# controller.net
KiCad netlist of a schematic drawn in EAGLE
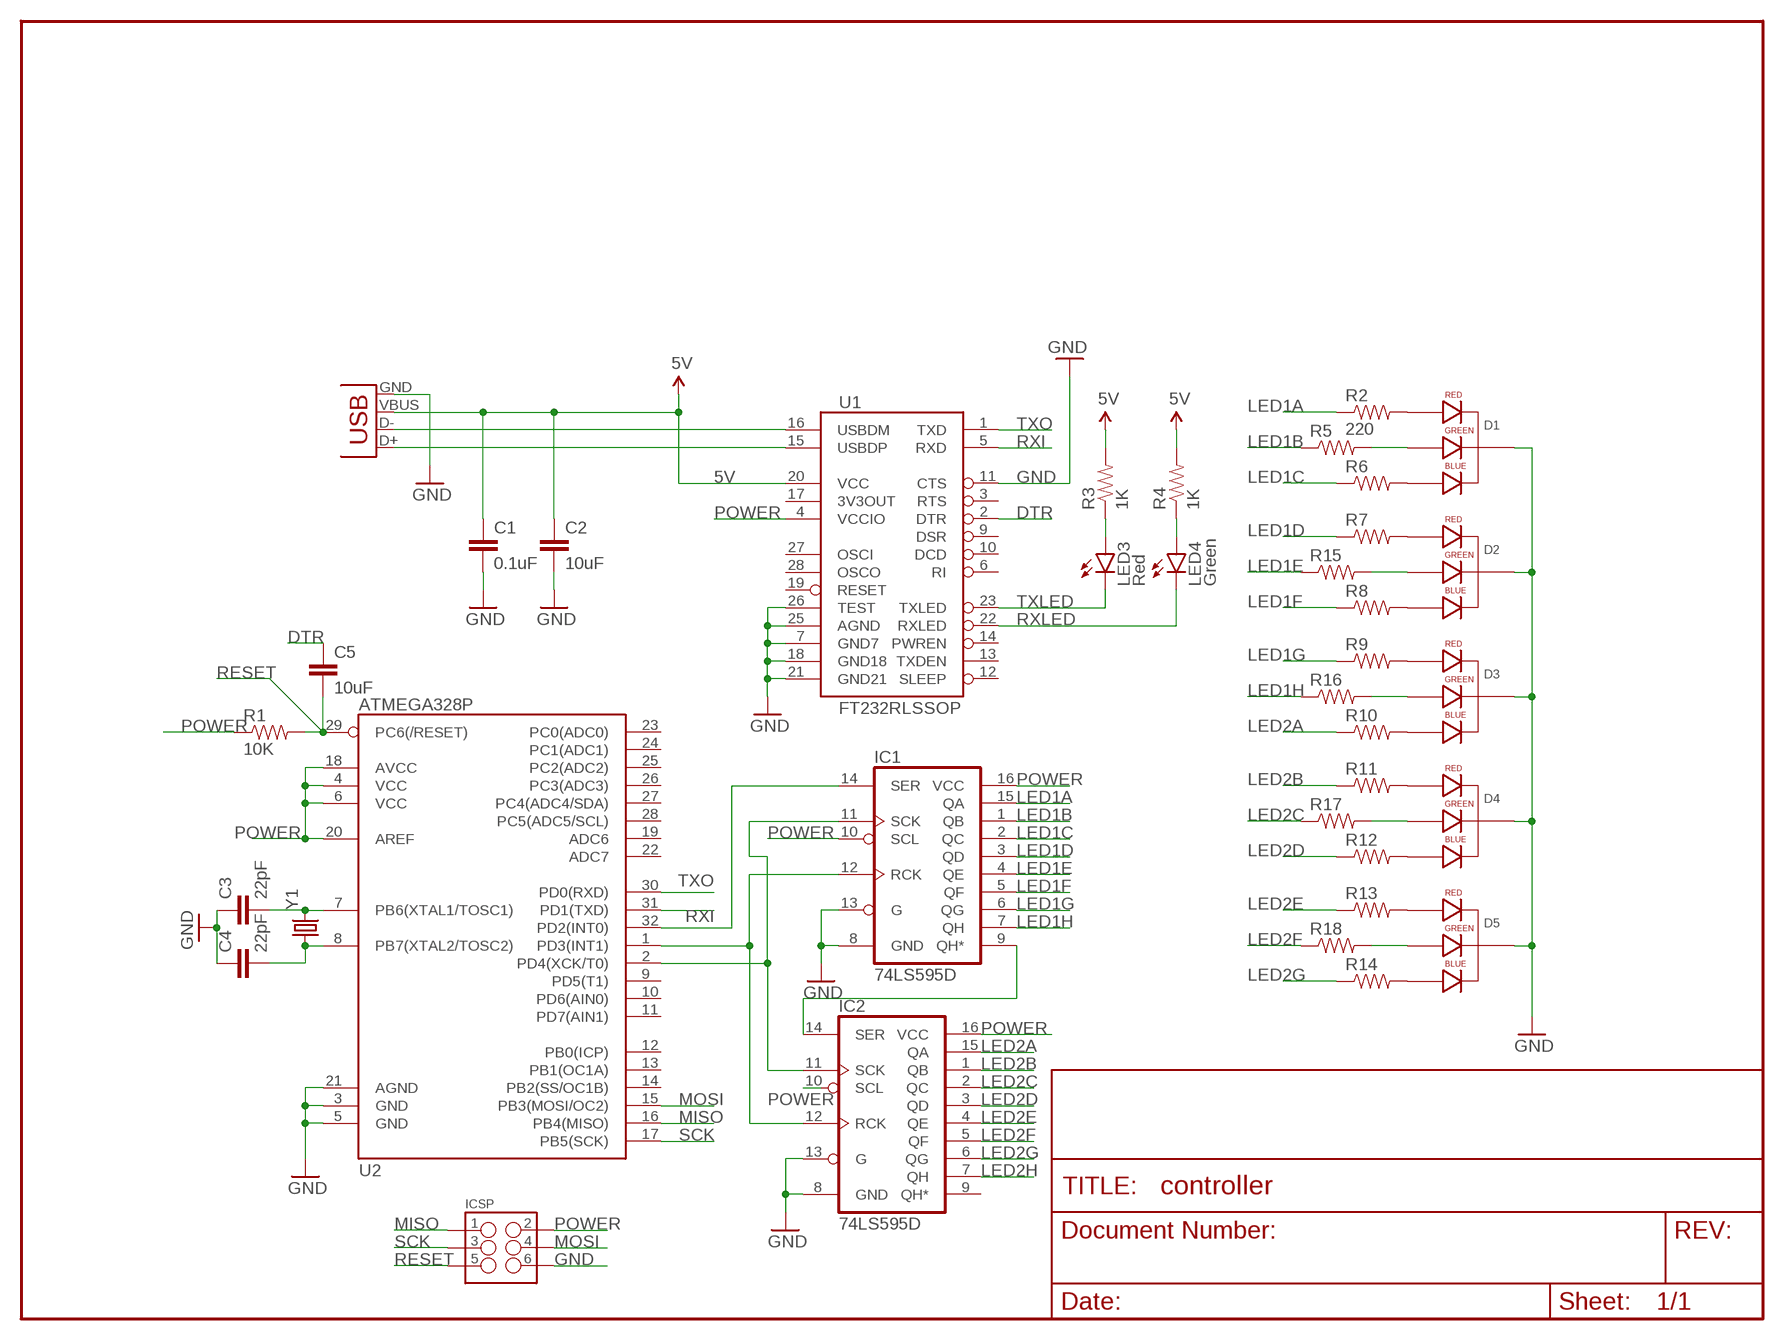
[diagram p0: schematic, sheet 1]

(export (version "E")
  (design (tool "Eeschema 10.0.6"))
  (components
    (comp (ref "C1")
      (value "0.1uF")
      (footprint "eagle-import:0805")
      (libsource (lib "eagle-import") (part "CAP0805"))
    )
    (comp (ref "C2")
      (value "10uF")
      (footprint "eagle-import:0805")
      (libsource (lib "eagle-import") (part "CAP0805"))
    )
    (comp (ref "C3")
      (value "22pF")
      (footprint "eagle-import:0805")
      (libsource (lib "eagle-import") (part "CAP0805"))
    )
    (comp (ref "C4")
      (value "22pF")
      (footprint "eagle-import:0805")
      (libsource (lib "eagle-import") (part "CAP0805"))
    )
    (comp (ref "C5")
      (value "10uF")
      (footprint "eagle-import:0805")
      (libsource (lib "eagle-import") (part "CAP0805"))
    )
    (comp (ref "D1")
      (value "LED-RGB-CC-THRUDIFFUSE")
      (footprint "eagle-import:LED-RGB-THRU")
      (libsource (lib "eagle-import") (part "LED-RGB-CC-THRUDIFFUSE"))
    )
    (comp (ref "D2")
      (value "LED-RGB-CC-THRUDIFFUSE")
      (footprint "eagle-import:LED-RGB-THRU")
      (libsource (lib "eagle-import") (part "LED-RGB-CC-THRUDIFFUSE"))
    )
    (comp (ref "D3")
      (value "LED-RGB-CC-THRUDIFFUSE")
      (footprint "eagle-import:LED-RGB-THRU")
      (libsource (lib "eagle-import") (part "LED-RGB-CC-THRUDIFFUSE"))
    )
    (comp (ref "D4")
      (value "LED-RGB-CC-THRUDIFFUSE")
      (footprint "eagle-import:LED-RGB-THRU")
      (libsource (lib "eagle-import") (part "LED-RGB-CC-THRUDIFFUSE"))
    )
    (comp (ref "D5")
      (value "LED-RGB-CC-THRUDIFFUSE")
      (footprint "eagle-import:LED-RGB-THRU")
      (libsource (lib "eagle-import") (part "LED-RGB-CC-THRUDIFFUSE"))
    )
    (comp (ref "IC1")
      (value "74LS595D")
      (footprint "eagle-import:SO16")
      (libsource (lib "eagle-import") (part "74595DLS"))
    )
    (comp (ref "IC2")
      (value "74LS595D")
      (footprint "eagle-import:SO16")
      (libsource (lib "eagle-import") (part "74595DLS"))
    )
    (comp (ref "ICSP")
      (value "M03X2POGO_PINS")
      (footprint "eagle-import:2X3_POGO")
      (libsource (lib "eagle-import") (part "M03X2POGO_PINS"))
    )
    (comp (ref "LED3")
      (value "Red")
      (footprint "eagle-import:LED-1206")
      (libsource (lib "eagle-import") (part "LED1206"))
    )
    (comp (ref "LED4")
      (value "Green")
      (footprint "eagle-import:LED-1206")
      (libsource (lib "eagle-import") (part "LED1206"))
    )
    (comp (ref "R1")
      (value "10K")
      (footprint "eagle-import:0805")
      (libsource (lib "eagle-import") (part "RESISTOR0805-RES"))
    )
    (comp (ref "R2")
      (value "220")
      (footprint "eagle-import:0805")
      (libsource (lib "eagle-import") (part "RESISTOR0805-RES"))
    )
    (comp (ref "R3")
      (value "1K")
      (footprint "eagle-import:0805")
      (libsource (lib "eagle-import") (part "RESISTOR0805-RES"))
    )
    (comp (ref "R4")
      (value "1K")
      (footprint "eagle-import:0805")
      (libsource (lib "eagle-import") (part "RESISTOR0805-RES"))
    )
    (comp (ref "R5")
      (value "RESISTOR0805-RES")
      (footprint "eagle-import:0805")
      (libsource (lib "eagle-import") (part "RESISTOR0805-RES"))
    )
    (comp (ref "R6")
      (value "RESISTOR0805-RES")
      (footprint "eagle-import:0805")
      (libsource (lib "eagle-import") (part "RESISTOR0805-RES"))
    )
    (comp (ref "R7")
      (value "RESISTOR0805-RES")
      (footprint "eagle-import:0805")
      (libsource (lib "eagle-import") (part "RESISTOR0805-RES"))
    )
    (comp (ref "R8")
      (value "RESISTOR0805-RES")
      (footprint "eagle-import:0805")
      (libsource (lib "eagle-import") (part "RESISTOR0805-RES"))
    )
    (comp (ref "R9")
      (value "RESISTOR0805-RES")
      (footprint "eagle-import:0805")
      (libsource (lib "eagle-import") (part "RESISTOR0805-RES"))
    )
    (comp (ref "R10")
      (value "RESISTOR0805-RES")
      (footprint "eagle-import:0805")
      (libsource (lib "eagle-import") (part "RESISTOR0805-RES"))
    )
    (comp (ref "R11")
      (value "RESISTOR0805-RES")
      (footprint "eagle-import:0805")
      (libsource (lib "eagle-import") (part "RESISTOR0805-RES"))
    )
    (comp (ref "R12")
      (value "RESISTOR0805-RES")
      (footprint "eagle-import:0805")
      (libsource (lib "eagle-import") (part "RESISTOR0805-RES"))
    )
    (comp (ref "R13")
      (value "RESISTOR0805-RES")
      (footprint "eagle-import:0805")
      (libsource (lib "eagle-import") (part "RESISTOR0805-RES"))
    )
    (comp (ref "R14")
      (value "RESISTOR0805-RES")
      (footprint "eagle-import:0805")
      (libsource (lib "eagle-import") (part "RESISTOR0805-RES"))
    )
    (comp (ref "R15")
      (value "RESISTOR0805-RES")
      (footprint "eagle-import:0805")
      (libsource (lib "eagle-import") (part "RESISTOR0805-RES"))
    )
    (comp (ref "R16")
      (value "RESISTOR0805-RES")
      (footprint "eagle-import:0805")
      (libsource (lib "eagle-import") (part "RESISTOR0805-RES"))
    )
    (comp (ref "R17")
      (value "RESISTOR0805-RES")
      (footprint "eagle-import:0805")
      (libsource (lib "eagle-import") (part "RESISTOR0805-RES"))
    )
    (comp (ref "R18")
      (value "RESISTOR0805-RES")
      (footprint "eagle-import:0805")
      (libsource (lib "eagle-import") (part "RESISTOR0805-RES"))
    )
    (comp (ref "U1")
      (value "FT232RLSSOP")
      (footprint "eagle-import:SSOP28DB")
      (libsource (lib "eagle-import") (part "FT232RLSSOP"))
    )
    (comp (ref "U2")
      (value "ATMEGA328P")
      (footprint "eagle-import:TQFP32-08")
      (libsource (lib "eagle-import") (part "ATMEGA328_SMT"))
    )
    (comp (ref "X2")
      (value "USB-SMD-NS")
      (footprint "eagle-import:USB-MINIB-NOSTOP")
      (libsource (lib "eagle-import") (part "USB-SMD-NS"))
    )
    (comp (ref "Y1")
      (value "CRYSTALHC49US")
      (footprint "eagle-import:HC49US")
      (libsource (lib "eagle-import") (part "CRYSTALHC49US"))
    )
  )
  (nets
    (net (code "1") (name "/DTR") (class "Default")
      (node (ref "C5") (pin "1") (pinfunction "1_1") (pintype "passive"))
      (node (ref "U1") (pin "2") (pinfunction "DTR_2") (pintype "output"))
    )
    (net (code "2") (name "/LED1A") (class "Default")
      (node (ref "IC1") (pin "15") (pinfunction "QA_15") (pintype "tri_state"))
      (node (ref "R2") (pin "1") (pinfunction "1_1") (pintype "passive"))
    )
    (net (code "3") (name "/LED1B") (class "Default")
      (node (ref "IC1") (pin "1") (pinfunction "QB_1") (pintype "tri_state"))
      (node (ref "R5") (pin "1") (pinfunction "1_1") (pintype "passive"))
    )
    (net (code "4") (name "/LED1C") (class "Default")
      (node (ref "IC1") (pin "2") (pinfunction "QC_2") (pintype "tri_state"))
      (node (ref "R6") (pin "1") (pinfunction "1_1") (pintype "passive"))
    )
    (net (code "5") (name "/LED1D") (class "Default")
      (node (ref "IC1") (pin "3") (pinfunction "QD_3") (pintype "tri_state"))
      (node (ref "R7") (pin "1") (pinfunction "1_1") (pintype "passive"))
    )
    (net (code "6") (name "/LED1E") (class "Default")
      (node (ref "IC1") (pin "4") (pinfunction "QE_4") (pintype "tri_state"))
      (node (ref "R15") (pin "1") (pinfunction "1_1") (pintype "passive"))
    )
    (net (code "7") (name "/LED1F") (class "Default")
      (node (ref "IC1") (pin "5") (pinfunction "QF_5") (pintype "tri_state"))
      (node (ref "R8") (pin "1") (pinfunction "1_1") (pintype "passive"))
    )
    (net (code "8") (name "/LED1G") (class "Default")
      (node (ref "IC1") (pin "6") (pinfunction "QG_6") (pintype "tri_state"))
      (node (ref "R9") (pin "1") (pinfunction "1_1") (pintype "passive"))
    )
    (net (code "9") (name "/LED1H") (class "Default")
      (node (ref "IC1") (pin "7") (pinfunction "QH_7") (pintype "tri_state"))
      (node (ref "R16") (pin "1") (pinfunction "1_1") (pintype "passive"))
    )
    (net (code "10") (name "/LED2A") (class "Default")
      (node (ref "IC2") (pin "15") (pinfunction "QA_15") (pintype "tri_state"))
      (node (ref "R10") (pin "1") (pinfunction "1_1") (pintype "passive"))
    )
    (net (code "11") (name "/LED2B") (class "Default")
      (node (ref "IC2") (pin "1") (pinfunction "QB_1") (pintype "tri_state"))
      (node (ref "R11") (pin "1") (pinfunction "1_1") (pintype "passive"))
    )
    (net (code "12") (name "/LED2C") (class "Default")
      (node (ref "IC2") (pin "2") (pinfunction "QC_2") (pintype "tri_state"))
      (node (ref "R17") (pin "1") (pinfunction "1_1") (pintype "passive"))
    )
    (net (code "13") (name "/LED2D") (class "Default")
      (node (ref "IC2") (pin "3") (pinfunction "QD_3") (pintype "tri_state"))
      (node (ref "R12") (pin "1") (pinfunction "1_1") (pintype "passive"))
    )
    (net (code "14") (name "/LED2E") (class "Default")
      (node (ref "IC2") (pin "4") (pinfunction "QE_4") (pintype "tri_state"))
      (node (ref "R13") (pin "1") (pinfunction "1_1") (pintype "passive"))
    )
    (net (code "15") (name "/LED2F") (class "Default")
      (node (ref "IC2") (pin "5") (pinfunction "QF_5") (pintype "tri_state"))
      (node (ref "R18") (pin "1") (pinfunction "1_1") (pintype "passive"))
    )
    (net (code "16") (name "/LED2G") (class "Default")
      (node (ref "IC2") (pin "6") (pinfunction "QG_6") (pintype "tri_state"))
      (node (ref "R14") (pin "1") (pinfunction "1_1") (pintype "passive"))
    )
    (net (code "17") (name "/LED2H") (class "Default")
      (node (ref "IC2") (pin "7") (pinfunction "QH_7") (pintype "tri_state"))
    )
    (net (code "18") (name "/MISO") (class "Default")
      (node (ref "ICSP") (pin "P$1") (pinfunction "1_P$1") (pintype "bidirectional"))
      (node (ref "U2") (pin "16") (pinfunction "PB4(MISO)_16") (pintype "bidirectional"))
    )
    (net (code "19") (name "/MOSI") (class "Default")
      (node (ref "ICSP") (pin "P$4") (pinfunction "4_P$4") (pintype "bidirectional"))
      (node (ref "U2") (pin "15") (pinfunction "PB3(MOSI/OC2)_15") (pintype "bidirectional"))
    )
    (net (code "20") (name "/POWER") (class "Default")
      (node (ref "IC1") (pin "10") (pinfunction "SCL_10") (pintype "input"))
      (node (ref "IC1") (pin "16") (pinfunction "VCC_16") (pintype "power_in"))
      (node (ref "IC2") (pin "10") (pinfunction "SCL_10") (pintype "input"))
      (node (ref "IC2") (pin "16") (pinfunction "VCC_16") (pintype "power_in"))
      (node (ref "ICSP") (pin "P$2") (pinfunction "2_P$2") (pintype "bidirectional"))
      (node (ref "R1") (pin "1") (pinfunction "1_1") (pintype "passive"))
      (node (ref "U1") (pin "4") (pinfunction "VCCIO_4") (pintype "power_in"))
      (node (ref "U2") (pin "18") (pinfunction "AVCC_18") (pintype "bidirectional"))
      (node (ref "U2") (pin "20") (pinfunction "AREF_20") (pintype "bidirectional"))
      (node (ref "U2") (pin "4") (pinfunction "VCC_4") (pintype "bidirectional"))
      (node (ref "U2") (pin "6") (pinfunction "VCC_6") (pintype "bidirectional"))
    )
    (net (code "21") (name "/RESET") (class "Default")
      (node (ref "C5") (pin "2") (pinfunction "2_2") (pintype "passive"))
      (node (ref "ICSP") (pin "P$5") (pinfunction "5_P$5") (pintype "bidirectional"))
      (node (ref "R1") (pin "2") (pinfunction "2_2") (pintype "passive"))
      (node (ref "U2") (pin "29") (pinfunction "PC6(/RESET)_29") (pintype "bidirectional"))
    )
    (net (code "22") (name "/RXI") (class "Default")
      (node (ref "U1") (pin "5") (pinfunction "RXD_5") (pintype "input"))
      (node (ref "U2") (pin "31") (pinfunction "PD1(TXD)_31") (pintype "bidirectional"))
    )
    (net (code "23") (name "/RXLED") (class "Default")
      (node (ref "LED4") (pin "C") (pinfunction "C_C") (pintype "passive"))
      (node (ref "U1") (pin "22") (pinfunction "RXLED_22") (pintype "input"))
    )
    (net (code "24") (name "/SCK") (class "Default")
      (node (ref "ICSP") (pin "P$3") (pinfunction "3_P$3") (pintype "bidirectional"))
      (node (ref "U2") (pin "17") (pinfunction "PB5(SCK)_17") (pintype "bidirectional"))
    )
    (net (code "25") (name "/TXLED") (class "Default")
      (node (ref "LED3") (pin "C") (pinfunction "C_C") (pintype "passive"))
      (node (ref "U1") (pin "23") (pinfunction "TXLED_23") (pintype "input"))
    )
    (net (code "26") (name "/TXO") (class "Default")
      (node (ref "U1") (pin "1") (pinfunction "TXD_1") (pintype "output"))
      (node (ref "U2") (pin "30") (pinfunction "PD0(RXD)_30") (pintype "bidirectional"))
    )
    (net (code "27") (name "5V") (class "Default")
      (node (ref "C1") (pin "1") (pinfunction "1_1") (pintype "passive"))
      (node (ref "C2") (pin "1") (pinfunction "1_1") (pintype "passive"))
      (node (ref "R3") (pin "2") (pinfunction "2_2") (pintype "passive"))
      (node (ref "R4") (pin "2") (pinfunction "2_2") (pintype "passive"))
      (node (ref "U1") (pin "20") (pinfunction "VCC_20") (pintype "power_in"))
      (node (ref "X2") (pin "VBUS") (pinfunction "VBUS_VBUS") (pintype "bidirectional"))
    )
    (net (code "28") (name "GND") (class "Default")
      (node (ref "C1") (pin "2") (pinfunction "2_2") (pintype "passive"))
      (node (ref "C2") (pin "2") (pinfunction "2_2") (pintype "passive"))
      (node (ref "C3") (pin "1") (pinfunction "1_1") (pintype "passive"))
      (node (ref "C4") (pin "1") (pinfunction "1_1") (pintype "passive"))
      (node (ref "D1") (pin "2") (pinfunction "CATHODE_2") (pintype "bidirectional"))
      (node (ref "D2") (pin "2") (pinfunction "CATHODE_2") (pintype "bidirectional"))
      (node (ref "D3") (pin "2") (pinfunction "CATHODE_2") (pintype "bidirectional"))
      (node (ref "D4") (pin "2") (pinfunction "CATHODE_2") (pintype "bidirectional"))
      (node (ref "D5") (pin "2") (pinfunction "CATHODE_2") (pintype "bidirectional"))
      (node (ref "IC1") (pin "13") (pinfunction "G_13") (pintype "input"))
      (node (ref "IC1") (pin "8") (pinfunction "GND_8") (pintype "power_in"))
      (node (ref "IC2") (pin "13") (pinfunction "G_13") (pintype "input"))
      (node (ref "IC2") (pin "8") (pinfunction "GND_8") (pintype "power_in"))
      (node (ref "ICSP") (pin "P$6") (pinfunction "6_P$6") (pintype "bidirectional"))
      (node (ref "U1") (pin "11") (pinfunction "CTS_11") (pintype "input"))
      (node (ref "U1") (pin "18") (pinfunction "GND18_18") (pintype "power_in"))
      (node (ref "U1") (pin "21") (pinfunction "GND21_21") (pintype "power_in"))
      (node (ref "U1") (pin "25") (pinfunction "AGND_25") (pintype "power_in"))
      (node (ref "U1") (pin "26") (pinfunction "TEST_26") (pintype "input"))
      (node (ref "U1") (pin "7") (pinfunction "GND7_7") (pintype "power_in"))
      (node (ref "U2") (pin "21") (pinfunction "AGND_21") (pintype "bidirectional"))
      (node (ref "U2") (pin "3") (pinfunction "GND_3") (pintype "bidirectional"))
      (node (ref "U2") (pin "5") (pinfunction "GND_5") (pintype "bidirectional"))
      (node (ref "X2") (pin "GND") (pinfunction "GND_GND") (pintype "bidirectional"))
    )
    (net (code "29") (name "Net-(D1-BLUE_CATHODE)") (class "Default")
      (node (ref "D1") (pin "4") (pinfunction "BLUE_CATHODE_4") (pintype "bidirectional"))
      (node (ref "R6") (pin "2") (pinfunction "2_2") (pintype "passive"))
    )
    (net (code "30") (name "Net-(D1-GREEN_CATHODE)") (class "Default")
      (node (ref "D1") (pin "3") (pinfunction "GREEN_CATHODE_3") (pintype "bidirectional"))
      (node (ref "R5") (pin "2") (pinfunction "2_2") (pintype "passive"))
    )
    (net (code "31") (name "Net-(D1-RED_CATHODE)") (class "Default")
      (node (ref "D1") (pin "1") (pinfunction "RED_CATHODE_1") (pintype "bidirectional"))
      (node (ref "R2") (pin "2") (pinfunction "2_2") (pintype "passive"))
    )
    (net (code "32") (name "Net-(D2-BLUE_CATHODE)") (class "Default")
      (node (ref "D2") (pin "4") (pinfunction "BLUE_CATHODE_4") (pintype "bidirectional"))
      (node (ref "R8") (pin "2") (pinfunction "2_2") (pintype "passive"))
    )
    (net (code "33") (name "Net-(D2-GREEN_CATHODE)") (class "Default")
      (node (ref "D2") (pin "3") (pinfunction "GREEN_CATHODE_3") (pintype "bidirectional"))
      (node (ref "R15") (pin "2") (pinfunction "2_2") (pintype "passive"))
    )
    (net (code "34") (name "Net-(D2-RED_CATHODE)") (class "Default")
      (node (ref "D2") (pin "1") (pinfunction "RED_CATHODE_1") (pintype "bidirectional"))
      (node (ref "R7") (pin "2") (pinfunction "2_2") (pintype "passive"))
    )
    (net (code "35") (name "Net-(D3-BLUE_CATHODE)") (class "Default")
      (node (ref "D3") (pin "4") (pinfunction "BLUE_CATHODE_4") (pintype "bidirectional"))
      (node (ref "R10") (pin "2") (pinfunction "2_2") (pintype "passive"))
    )
    (net (code "36") (name "Net-(D3-GREEN_CATHODE)") (class "Default")
      (node (ref "D3") (pin "3") (pinfunction "GREEN_CATHODE_3") (pintype "bidirectional"))
      (node (ref "R16") (pin "2") (pinfunction "2_2") (pintype "passive"))
    )
    (net (code "37") (name "Net-(D3-RED_CATHODE)") (class "Default")
      (node (ref "D3") (pin "1") (pinfunction "RED_CATHODE_1") (pintype "bidirectional"))
      (node (ref "R9") (pin "2") (pinfunction "2_2") (pintype "passive"))
    )
    (net (code "38") (name "Net-(D4-BLUE_CATHODE)") (class "Default")
      (node (ref "D4") (pin "4") (pinfunction "BLUE_CATHODE_4") (pintype "bidirectional"))
      (node (ref "R12") (pin "2") (pinfunction "2_2") (pintype "passive"))
    )
    (net (code "39") (name "Net-(D4-GREEN_CATHODE)") (class "Default")
      (node (ref "D4") (pin "3") (pinfunction "GREEN_CATHODE_3") (pintype "bidirectional"))
      (node (ref "R17") (pin "2") (pinfunction "2_2") (pintype "passive"))
    )
    (net (code "40") (name "Net-(D4-RED_CATHODE)") (class "Default")
      (node (ref "D4") (pin "1") (pinfunction "RED_CATHODE_1") (pintype "bidirectional"))
      (node (ref "R11") (pin "2") (pinfunction "2_2") (pintype "passive"))
    )
    (net (code "41") (name "Net-(D5-BLUE_CATHODE)") (class "Default")
      (node (ref "D5") (pin "4") (pinfunction "BLUE_CATHODE_4") (pintype "bidirectional"))
      (node (ref "R14") (pin "2") (pinfunction "2_2") (pintype "passive"))
    )
    (net (code "42") (name "Net-(D5-GREEN_CATHODE)") (class "Default")
      (node (ref "D5") (pin "3") (pinfunction "GREEN_CATHODE_3") (pintype "bidirectional"))
      (node (ref "R18") (pin "2") (pinfunction "2_2") (pintype "passive"))
    )
    (net (code "43") (name "Net-(D5-RED_CATHODE)") (class "Default")
      (node (ref "D5") (pin "1") (pinfunction "RED_CATHODE_1") (pintype "bidirectional"))
      (node (ref "R13") (pin "2") (pinfunction "2_2") (pintype "passive"))
    )
    (net (code "44") (name "Net-(IC1-QH*)") (class "Default")
      (node (ref "IC1") (pin "9") (pinfunction "QH*_9") (pintype "tri_state"))
      (node (ref "IC2") (pin "14") (pinfunction "SER_14") (pintype "input"))
    )
    (net (code "45") (name "Net-(IC1-RCK)") (class "Default")
      (node (ref "IC1") (pin "12") (pinfunction "RCK_12") (pintype "input"))
      (node (ref "IC2") (pin "12") (pinfunction "RCK_12") (pintype "input"))
      (node (ref "U2") (pin "1") (pinfunction "PD3(INT1)_1") (pintype "bidirectional"))
    )
    (net (code "46") (name "Net-(IC1-SCK)") (class "Default")
      (node (ref "IC1") (pin "11") (pinfunction "SCK_11") (pintype "input"))
      (node (ref "IC2") (pin "11") (pinfunction "SCK_11") (pintype "input"))
      (node (ref "U2") (pin "2") (pinfunction "PD4(XCK/T0)_2") (pintype "bidirectional"))
    )
    (net (code "47") (name "Net-(IC1-SER)") (class "Default")
      (node (ref "IC1") (pin "14") (pinfunction "SER_14") (pintype "input"))
      (node (ref "U2") (pin "32") (pinfunction "PD2(INT0)_32") (pintype "bidirectional"))
    )
    (net (code "48") (name "Net-(LED3-PadA)") (class "Default")
      (node (ref "LED3") (pin "A") (pinfunction "A_A") (pintype "passive"))
      (node (ref "R3") (pin "1") (pinfunction "1_1") (pintype "passive"))
    )
    (net (code "49") (name "Net-(LED4-PadA)") (class "Default")
      (node (ref "LED4") (pin "A") (pinfunction "A_A") (pintype "passive"))
      (node (ref "R4") (pin "1") (pinfunction "1_1") (pintype "passive"))
    )
    (net (code "50") (name "Net-(U1-USBDM)") (class "Default")
      (node (ref "U1") (pin "16") (pinfunction "USBDM_16") (pintype "bidirectional"))
      (node (ref "X2") (pin "D-") (pinfunction "D-_D-") (pintype "bidirectional"))
    )
    (net (code "51") (name "Net-(U1-USBDP)") (class "Default")
      (node (ref "U1") (pin "15") (pinfunction "USBDP_15") (pintype "bidirectional"))
      (node (ref "X2") (pin "D+") (pinfunction "D+_D+") (pintype "bidirectional"))
    )
    (net (code "52") (name "Net-(U2-PB6(XTAL1{slash}TOSC1))") (class "Default")
      (node (ref "C3") (pin "2") (pinfunction "2_2") (pintype "passive"))
      (node (ref "U2") (pin "7") (pinfunction "PB6(XTAL1/TOSC1)_7") (pintype "bidirectional"))
      (node (ref "Y1") (pin "2") (pinfunction "2_2") (pintype "passive"))
    )
    (net (code "53") (name "Net-(U2-PB7(XTAL2{slash}TOSC2))") (class "Default")
      (node (ref "C4") (pin "2") (pinfunction "2_2") (pintype "passive"))
      (node (ref "U2") (pin "8") (pinfunction "PB7(XTAL2/TOSC2)_8") (pintype "bidirectional"))
      (node (ref "Y1") (pin "1") (pinfunction "1_1") (pintype "passive"))
    )
    (net (code "54") (name "unconnected-(IC2-QH*-Pad9)") (class "Default")
      (node (ref "IC2") (pin "9") (pinfunction "QH*_9") (pintype "tri_state"))
    )
    (net (code "55") (name "unconnected-(U1-3V3OUT-Pad17)") (class "Default")
      (node (ref "U1") (pin "17") (pinfunction "3V3OUT_17") (pintype "output"))
    )
    (net (code "56") (name "unconnected-(U1-DCD-Pad10)") (class "Default")
      (node (ref "U1") (pin "10") (pinfunction "DCD_10") (pintype "input"))
    )
    (net (code "57") (name "unconnected-(U1-DSR-Pad9)") (class "Default")
      (node (ref "U1") (pin "9") (pinfunction "DSR_9") (pintype "input"))
    )
    (net (code "58") (name "unconnected-(U1-OSCI-Pad27)") (class "Default")
      (node (ref "U1") (pin "27") (pinfunction "OSCI_27") (pintype "input"))
    )
    (net (code "59") (name "unconnected-(U1-OSCO-Pad28)") (class "Default")
      (node (ref "U1") (pin "28") (pinfunction "OSCO_28") (pintype "output"))
    )
    (net (code "60") (name "unconnected-(U1-PWREN-Pad14)") (class "Default")
      (node (ref "U1") (pin "14") (pinfunction "PWREN_14") (pintype "input"))
    )
    (net (code "61") (name "unconnected-(U1-RESET-Pad19)") (class "Default")
      (node (ref "U1") (pin "19") (pinfunction "RESET_19") (pintype "input"))
    )
    (net (code "62") (name "unconnected-(U1-RI-Pad6)") (class "Default")
      (node (ref "U1") (pin "6") (pinfunction "RI_6") (pintype "input"))
    )
    (net (code "63") (name "unconnected-(U1-RTS-Pad3)") (class "Default")
      (node (ref "U1") (pin "3") (pinfunction "RTS_3") (pintype "output"))
    )
    (net (code "64") (name "unconnected-(U1-SLEEP-Pad12)") (class "Default")
      (node (ref "U1") (pin "12") (pinfunction "SLEEP_12") (pintype "input"))
    )
    (net (code "65") (name "unconnected-(U1-TXDEN-Pad13)") (class "Default")
      (node (ref "U1") (pin "13") (pinfunction "TXDEN_13") (pintype "input"))
    )
    (net (code "66") (name "unconnected-(U2-ADC6-Pad19)") (class "Default")
      (node (ref "U2") (pin "19") (pinfunction "ADC6_19") (pintype "bidirectional"))
    )
    (net (code "67") (name "unconnected-(U2-ADC7-Pad22)") (class "Default")
      (node (ref "U2") (pin "22") (pinfunction "ADC7_22") (pintype "bidirectional"))
    )
    (net (code "68") (name "unconnected-(U2-PB0(ICP)-Pad12)") (class "Default")
      (node (ref "U2") (pin "12") (pinfunction "PB0(ICP)_12") (pintype "bidirectional"))
    )
    (net (code "69") (name "unconnected-(U2-PB1(OC1A)-Pad13)") (class "Default")
      (node (ref "U2") (pin "13") (pinfunction "PB1(OC1A)_13") (pintype "bidirectional"))
    )
    (net (code "70") (name "unconnected-(U2-PB2(SS{slash}OC1B)-Pad14)") (class "Default")
      (node (ref "U2") (pin "14") (pinfunction "PB2(SS/OC1B)_14") (pintype "bidirectional"))
    )
    (net (code "71") (name "unconnected-(U2-PC0(ADC0)-Pad23)") (class "Default")
      (node (ref "U2") (pin "23") (pinfunction "PC0(ADC0)_23") (pintype "bidirectional"))
    )
    (net (code "72") (name "unconnected-(U2-PC1(ADC1)-Pad24)") (class "Default")
      (node (ref "U2") (pin "24") (pinfunction "PC1(ADC1)_24") (pintype "bidirectional"))
    )
    (net (code "73") (name "unconnected-(U2-PC2(ADC2)-Pad25)") (class "Default")
      (node (ref "U2") (pin "25") (pinfunction "PC2(ADC2)_25") (pintype "bidirectional"))
    )
    (net (code "74") (name "unconnected-(U2-PC3(ADC3)-Pad26)") (class "Default")
      (node (ref "U2") (pin "26") (pinfunction "PC3(ADC3)_26") (pintype "bidirectional"))
    )
    (net (code "75") (name "unconnected-(U2-PC4(ADC4{slash}SDA)-Pad27)") (class "Default")
      (node (ref "U2") (pin "27") (pinfunction "PC4(ADC4/SDA)_27") (pintype "bidirectional"))
    )
    (net (code "76") (name "unconnected-(U2-PC5(ADC5{slash}SCL)-Pad28)") (class "Default")
      (node (ref "U2") (pin "28") (pinfunction "PC5(ADC5/SCL)_28") (pintype "bidirectional"))
    )
    (net (code "77") (name "unconnected-(U2-PD5(T1)-Pad9)") (class "Default")
      (node (ref "U2") (pin "9") (pinfunction "PD5(T1)_9") (pintype "bidirectional"))
    )
    (net (code "78") (name "unconnected-(U2-PD6(AIN0)-Pad10)") (class "Default")
      (node (ref "U2") (pin "10") (pinfunction "PD6(AIN0)_10") (pintype "bidirectional"))
    )
    (net (code "79") (name "unconnected-(U2-PD7(AIN1)-Pad11)") (class "Default")
      (node (ref "U2") (pin "11") (pinfunction "PD7(AIN1)_11") (pintype "bidirectional"))
    )
  )
)
